# BM1370.net
KiCad netlist of a schematic drawn in Altium Designer
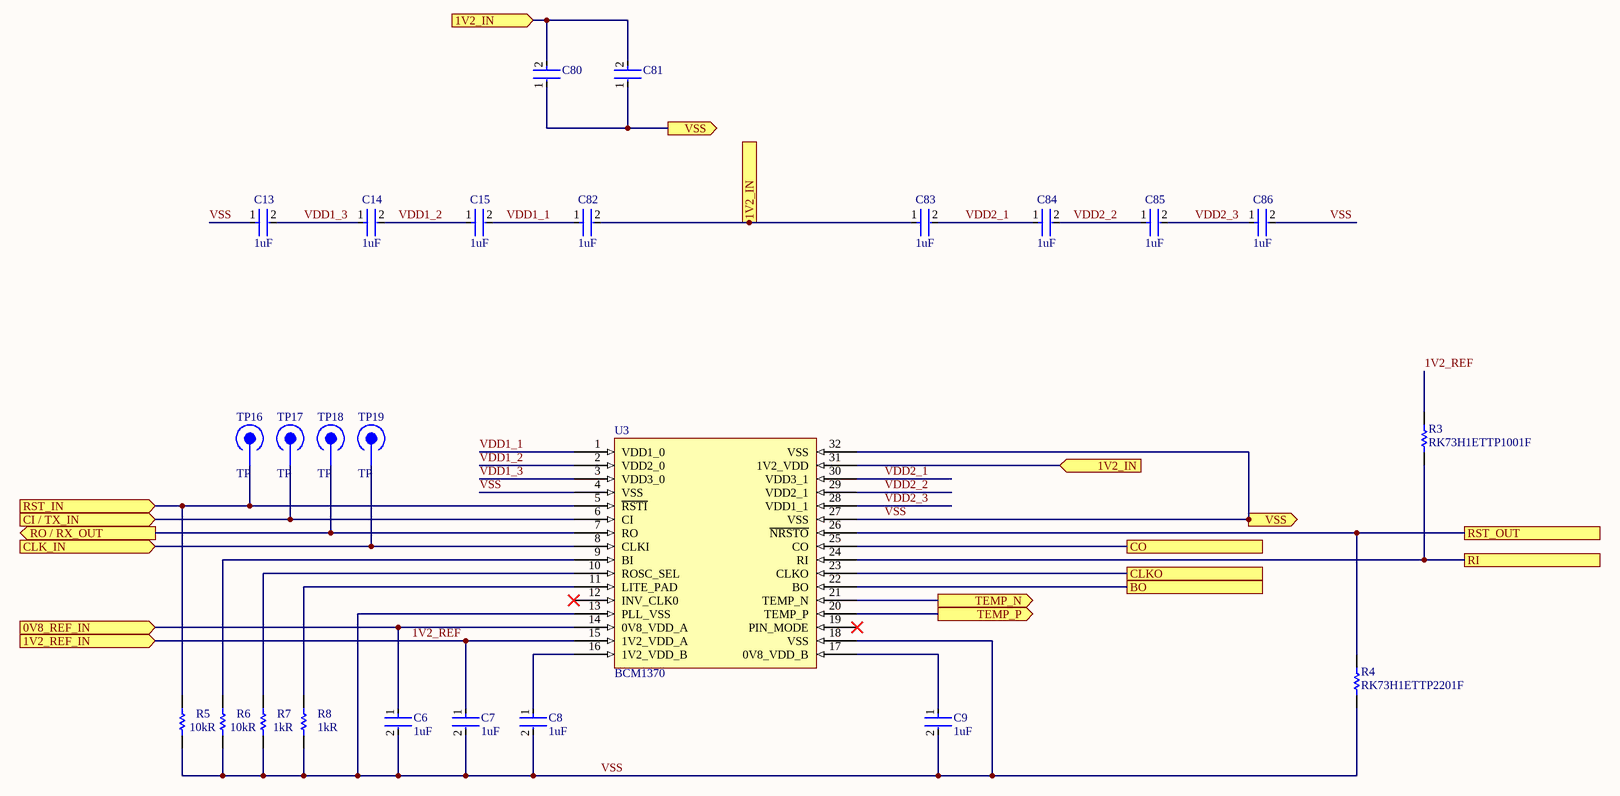
[diagram p0: BM1370.SchDoc]

(export (version "E")
  (design (tool "Eeschema 10.0.6"))
  (components
    (comp (ref "C6")
      (value "1uF")
      (footprint "FP-0402-L_1_0_0_05-W_0_5-MFG")
      (fields (field (name "MANUFACTURER") "Taiyo Yuden") (field (name "Comment") "EMK105BJ105KV-F"))
      (libsource (lib "Digital Shovel") (part "b4654b650e69147ec39a6b967a45e02"))
    )
    (comp (ref "C7")
      (value "1uF")
      (footprint "FP-0402-L_1_0_0_05-W_0_5-MFG")
      (fields (field (name "MANUFACTURER") "Taiyo Yuden") (field (name "Comment") "EMK105BJ105KV-F"))
      (libsource (lib "Digital Shovel") (part "b4654b650e69147ec39a6b967a45e02"))
    )
    (comp (ref "C8")
      (value "1uF")
      (footprint "FP-0402-L_1_0_0_05-W_0_5-MFG")
      (fields (field (name "MANUFACTURER") "Taiyo Yuden") (field (name "Comment") "EMK105BJ105KV-F"))
      (libsource (lib "Digital Shovel") (part "b4654b650e69147ec39a6b967a45e02"))
    )
    (comp (ref "C9")
      (value "1uF")
      (footprint "FP-0402-L_1_0_0_05-W_0_5-MFG")
      (fields (field (name "MANUFACTURER") "Taiyo Yuden") (field (name "Comment") "EMK105BJ105KV-F"))
      (libsource (lib "Digital Shovel") (part "b4654b650e69147ec39a6b967a45e02"))
    )
    (comp (ref "C13")
      (value "1uF")
      (footprint "FP-0402-L_1_0_0_05-W_0_5-MFG")
      (fields (field (name "MANUFACTURER") "Taiyo Yuden") (field (name "Comment") "EMK105BJ105KV-F"))
      (libsource (lib "Digital Shovel") (part "b4654b650e69147ec39a6b967a45e02"))
    )
    (comp (ref "C14")
      (value "1uF")
      (footprint "FP-0402-L_1_0_0_05-W_0_5-MFG")
      (fields (field (name "MANUFACTURER") "Taiyo Yuden") (field (name "Comment") "EMK105BJ105KV-F"))
      (libsource (lib "Digital Shovel") (part "b4654b650e69147ec39a6b967a45e02"))
    )
    (comp (ref "C15")
      (value "1uF")
      (footprint "FP-0402-L_1_0_0_05-W_0_5-MFG")
      (fields (field (name "MANUFACTURER") "Taiyo Yuden") (field (name "Comment") "EMK105BJ105KV-F"))
      (libsource (lib "Digital Shovel") (part "b4654b650e69147ec39a6b967a45e02"))
    )
    (comp (ref "C80")
      (value "GRM31CR60J107MEA8K")
      (footprint "FP-GRM31C-0_3-e0_3_0_8-IPC_A")
      (fields (field (name "MANUFACTURER") "Murata"))
      (libsource (lib "Digital Shovel") (part "f23184f103b6ebe33a8c269c53dcba6"))
    )
    (comp (ref "C81")
      (value "GRM31CR60J107MEA8K")
      (footprint "FP-GRM31C-0_3-e0_3_0_8-IPC_A")
      (fields (field (name "MANUFACTURER") "Murata"))
      (libsource (lib "Digital Shovel") (part "f23184f103b6ebe33a8c269c53dcba6"))
    )
    (comp (ref "C82")
      (value "1uF")
      (footprint "FP-0402-L_1_0_0_05-W_0_5-MFG")
      (fields (field (name "MANUFACTURER") "Taiyo Yuden") (field (name "Comment") "EMK105BJ105KV-F"))
      (libsource (lib "Digital Shovel") (part "b4654b650e69147ec39a6b967a45e02"))
    )
    (comp (ref "C83")
      (value "1uF")
      (footprint "FP-0402-L_1_0_0_05-W_0_5-MFG")
      (fields (field (name "MANUFACTURER") "Taiyo Yuden") (field (name "Comment") "EMK105BJ105KV-F"))
      (libsource (lib "Digital Shovel") (part "b4654b650e69147ec39a6b967a45e02"))
    )
    (comp (ref "C84")
      (value "1uF")
      (footprint "FP-0402-L_1_0_0_05-W_0_5-MFG")
      (fields (field (name "MANUFACTURER") "Taiyo Yuden") (field (name "Comment") "EMK105BJ105KV-F"))
      (libsource (lib "Digital Shovel") (part "b4654b650e69147ec39a6b967a45e02"))
    )
    (comp (ref "C85")
      (value "1uF")
      (footprint "FP-0402-L_1_0_0_05-W_0_5-MFG")
      (fields (field (name "MANUFACTURER") "Taiyo Yuden") (field (name "Comment") "EMK105BJ105KV-F"))
      (libsource (lib "Digital Shovel") (part "b4654b650e69147ec39a6b967a45e02"))
    )
    (comp (ref "C86")
      (value "1uF")
      (footprint "FP-0402-L_1_0_0_05-W_0_5-MFG")
      (fields (field (name "MANUFACTURER") "Taiyo Yuden") (field (name "Comment") "EMK105BJ105KV-F"))
      (libsource (lib "Digital Shovel") (part "b4654b650e69147ec39a6b967a45e02"))
    )
    (comp (ref "R3")
      (value "RK73H1ETTP1001F")
      (footprint "RESC1005X40X25LL10T10")
      (libsource (lib "Digital Shovel") (part "RES"))
    )
    (comp (ref "R4")
      (value "RK73H1ETTP2201F")
      (footprint "RK73H1ETTP2201F-Footprint-1")
      (fields (field (name "MANUFACTURER") "KOA Speer"))
      (libsource (lib "Digital Shovel") (part "RES"))
    )
    (comp (ref "R5")
      (value "10kR")
      (footprint "RESC1005X40X25LL10T10")
      (fields (field (name "Comment") "RK73H1ETTP1002F"))
      (libsource (lib "Digital Shovel") (part "RES"))
    )
    (comp (ref "R6")
      (value "10kR")
      (footprint "RESC1005X40X25LL10T10")
      (fields (field (name "Comment") "RK73H1ETTP1002F"))
      (libsource (lib "Digital Shovel") (part "RES"))
    )
    (comp (ref "R7")
      (value "1kR")
      (footprint "RESC1005X40X25LL10T10")
      (fields (field (name "Comment") "RK73H1ETTP1001F"))
      (libsource (lib "Digital Shovel") (part "RES"))
    )
    (comp (ref "R8")
      (value "1kR")
      (footprint "RESC1005X40X25LL10T10")
      (fields (field (name "Comment") "RK73H1ETTP1001F"))
      (libsource (lib "Digital Shovel") (part "RES"))
    )
    (comp (ref "TP16")
      (value "TP")
      (footprint "TP-Footprint-1")
      (description "digital shovel test point")
      (libsource (lib "Digital Shovel") (part "TP-Symbol-1"))
    )
    (comp (ref "TP17")
      (value "TP")
      (footprint "TP-Footprint-1")
      (description "digital shovel test point")
      (libsource (lib "Digital Shovel") (part "TP-Symbol-1"))
    )
    (comp (ref "TP18")
      (value "TP")
      (footprint "TP-Footprint-1")
      (description "digital shovel test point")
      (libsource (lib "Digital Shovel") (part "TP-Symbol-1"))
    )
    (comp (ref "TP19")
      (value "TP")
      (footprint "TP-Footprint-1")
      (description "digital shovel test point")
      (libsource (lib "Digital Shovel") (part "TP-Symbol-1"))
    )
    (comp (ref "U3")
      (value "BCM1370")
      (footprint "BCM1370-Footprint-1")
      (description "BCM1370 Miner Chip")
      (fields (field (name "MANUFACTURER") "Bitmain"))
      (libsource (lib "Digital Shovel") (part "BCM1370-Symbol-1"))
    )
  )
  (nets
    (net (code "1") (name "/0V8_REF_IN") (class "Default")
      (node (ref "C6") (pin "1") (pinfunction "1_1") (pintype "passive"))
      (node (ref "U3") (pin "14") (pinfunction "0V8_VDD_A_14") (pintype "input"))
    )
    (net (code "2") (name "/1V2_IN") (class "Default")
      (node (ref "C80") (pin "2") (pinfunction "2_2") (pintype "passive"))
      (node (ref "C81") (pin "2") (pinfunction "2_2") (pintype "passive"))
      (node (ref "C82") (pin "2") (pinfunction "2_2") (pintype "passive"))
      (node (ref "C83") (pin "1") (pinfunction "1_1") (pintype "passive"))
      (node (ref "U3") (pin "31") (pinfunction "1V2_VDD_31") (pintype "input"))
    )
    (net (code "3") (name "/1V2_REF") (class "Default")
      (node (ref "C7") (pin "1") (pinfunction "1_1") (pintype "passive"))
      (node (ref "R3") (pin "2") (pinfunction "2_2") (pintype "passive"))
      (node (ref "U3") (pin "15") (pinfunction "1V2_VDD_A_15") (pintype "input"))
    )
    (net (code "4") (name "/BO") (class "Default")
      (node (ref "U3") (pin "22") (pinfunction "BO_22") (pintype "input"))
    )
    (net (code "5") (name "/CI {slash} TX_IN") (class "Default")
      (node (ref "TP17") (pin "1") (pintype "passive"))
      (node (ref "U3") (pin "6") (pinfunction "CI_6") (pintype "input"))
    )
    (net (code "6") (name "/CLKO") (class "Default")
      (node (ref "U3") (pin "23") (pinfunction "CLKO_23") (pintype "input"))
    )
    (net (code "7") (name "/CLK_IN") (class "Default")
      (node (ref "TP19") (pin "1") (pintype "passive"))
      (node (ref "U3") (pin "8") (pinfunction "CLKI_8") (pintype "input"))
    )
    (net (code "8") (name "/CO") (class "Default")
      (node (ref "U3") (pin "25") (pinfunction "CO_25") (pintype "input"))
    )
    (net (code "9") (name "/RI") (class "Default")
      (node (ref "R3") (pin "1") (pinfunction "1_1") (pintype "passive"))
      (node (ref "U3") (pin "24") (pinfunction "RI_24") (pintype "input"))
    )
    (net (code "10") (name "/RO {slash} RX_OUT") (class "Default")
      (node (ref "TP18") (pin "1") (pintype "passive"))
      (node (ref "U3") (pin "7") (pinfunction "RO_7") (pintype "input"))
    )
    (net (code "11") (name "/RST_IN") (class "Default")
      (node (ref "R5") (pin "2") (pinfunction "2_2") (pintype "passive"))
      (node (ref "TP16") (pin "1") (pintype "passive"))
      (node (ref "U3") (pin "5") (pinfunction "~{RSTI}_5") (pintype "input"))
    )
    (net (code "12") (name "/RST_OUT") (class "Default")
      (node (ref "R4") (pin "2") (pinfunction "2_2") (pintype "passive"))
      (node (ref "U3") (pin "26") (pinfunction "~{NRSTO}_26") (pintype "input"))
    )
    (net (code "13") (name "/TEMP_N") (class "Default")
      (node (ref "U3") (pin "21") (pinfunction "TEMP_N_21") (pintype "input"))
    )
    (net (code "14") (name "/TEMP_P") (class "Default")
      (node (ref "U3") (pin "20") (pinfunction "TEMP_P_20") (pintype "input"))
    )
    (net (code "15") (name "/VDD1_1") (class "Default")
      (node (ref "C15") (pin "2") (pinfunction "2_2") (pintype "passive"))
      (node (ref "C82") (pin "1") (pinfunction "1_1") (pintype "passive"))
      (node (ref "U3") (pin "1") (pinfunction "VDD1_0_1") (pintype "input"))
    )
    (net (code "16") (name "/VDD1_2") (class "Default")
      (node (ref "C14") (pin "2") (pinfunction "2_2") (pintype "passive"))
      (node (ref "C15") (pin "1") (pinfunction "1_1") (pintype "passive"))
      (node (ref "U3") (pin "2") (pinfunction "VDD2_0_2") (pintype "input"))
    )
    (net (code "17") (name "/VDD1_3") (class "Default")
      (node (ref "C13") (pin "2") (pinfunction "2_2") (pintype "passive"))
      (node (ref "C14") (pin "1") (pinfunction "1_1") (pintype "passive"))
      (node (ref "U3") (pin "3") (pinfunction "VDD3_0_3") (pintype "input"))
    )
    (net (code "18") (name "/VDD2_1") (class "Default")
      (node (ref "C83") (pin "2") (pinfunction "2_2") (pintype "passive"))
      (node (ref "C84") (pin "1") (pinfunction "1_1") (pintype "passive"))
      (node (ref "U3") (pin "30") (pinfunction "VDD3_1_30") (pintype "input"))
    )
    (net (code "19") (name "/VDD2_2") (class "Default")
      (node (ref "C84") (pin "2") (pinfunction "2_2") (pintype "passive"))
      (node (ref "C85") (pin "1") (pinfunction "1_1") (pintype "passive"))
      (node (ref "U3") (pin "29") (pinfunction "VDD2_1_29") (pintype "input"))
    )
    (net (code "20") (name "/VDD2_3") (class "Default")
      (node (ref "C85") (pin "2") (pinfunction "2_2") (pintype "passive"))
      (node (ref "C86") (pin "1") (pinfunction "1_1") (pintype "passive"))
      (node (ref "U3") (pin "28") (pinfunction "VDD1_1_28") (pintype "input"))
    )
    (net (code "21") (name "/VSS") (class "Default")
      (node (ref "C13") (pin "1") (pinfunction "1_1") (pintype "passive"))
      (node (ref "C6") (pin "2") (pinfunction "2_2") (pintype "passive"))
      (node (ref "C7") (pin "2") (pinfunction "2_2") (pintype "passive"))
      (node (ref "C8") (pin "2") (pinfunction "2_2") (pintype "passive"))
      (node (ref "C80") (pin "1") (pinfunction "1_1") (pintype "passive"))
      (node (ref "C81") (pin "1") (pinfunction "1_1") (pintype "passive"))
      (node (ref "C86") (pin "2") (pinfunction "2_2") (pintype "passive"))
      (node (ref "C9") (pin "2") (pinfunction "2_2") (pintype "passive"))
      (node (ref "R4") (pin "1") (pinfunction "1_1") (pintype "passive"))
      (node (ref "R5") (pin "1") (pinfunction "1_1") (pintype "passive"))
      (node (ref "R6") (pin "1") (pinfunction "1_1") (pintype "passive"))
      (node (ref "R7") (pin "1") (pinfunction "1_1") (pintype "passive"))
      (node (ref "R8") (pin "1") (pinfunction "1_1") (pintype "passive"))
      (node (ref "U3") (pin "13") (pinfunction "PLL_VSS_13") (pintype "input"))
      (node (ref "U3") (pin "18") (pinfunction "VSS_18") (pintype "input"))
      (node (ref "U3") (pin "27") (pinfunction "VSS_27") (pintype "input"))
      (node (ref "U3") (pin "32") (pinfunction "VSS_32") (pintype "input"))
      (node (ref "U3") (pin "4") (pinfunction "VSS_4") (pintype "input"))
    )
    (net (code "22") (name "Net-(U3-0V8_VDD_B)") (class "Default")
      (node (ref "C9") (pin "1") (pinfunction "1_1") (pintype "passive"))
      (node (ref "U3") (pin "17") (pinfunction "0V8_VDD_B_17") (pintype "input"))
    )
    (net (code "23") (name "Net-(U3-1V2_VDD_B)") (class "Default")
      (node (ref "C8") (pin "1") (pinfunction "1_1") (pintype "passive"))
      (node (ref "U3") (pin "16") (pinfunction "1V2_VDD_B_16") (pintype "input"))
    )
    (net (code "24") (name "Net-(U3-BI)") (class "Default")
      (node (ref "R6") (pin "2") (pinfunction "2_2") (pintype "passive"))
      (node (ref "U3") (pin "9") (pinfunction "BI_9") (pintype "input"))
    )
    (net (code "25") (name "Net-(U3-LITE_PAD)") (class "Default")
      (node (ref "R8") (pin "2") (pinfunction "2_2") (pintype "passive"))
      (node (ref "U3") (pin "11") (pinfunction "LITE_PAD_11") (pintype "input"))
    )
    (net (code "26") (name "Net-(U3-ROSC_SEL)") (class "Default")
      (node (ref "R7") (pin "2") (pinfunction "2_2") (pintype "passive"))
      (node (ref "U3") (pin "10") (pinfunction "ROSC_SEL_10") (pintype "input"))
    )
    (net (code "27") (name "unconnected-(U3-INV_CLK0-Pad12)") (class "Default")
      (node (ref "U3") (pin "12") (pinfunction "INV_CLK0_12") (pintype "input+no_connect"))
    )
    (net (code "28") (name "unconnected-(U3-PIN_MODE-Pad19)") (class "Default")
      (node (ref "U3") (pin "19") (pinfunction "PIN_MODE_19") (pintype "input+no_connect"))
    )
  )
)
